# lichtla.net
KiCad netlist of a schematic drawn in EAGLE
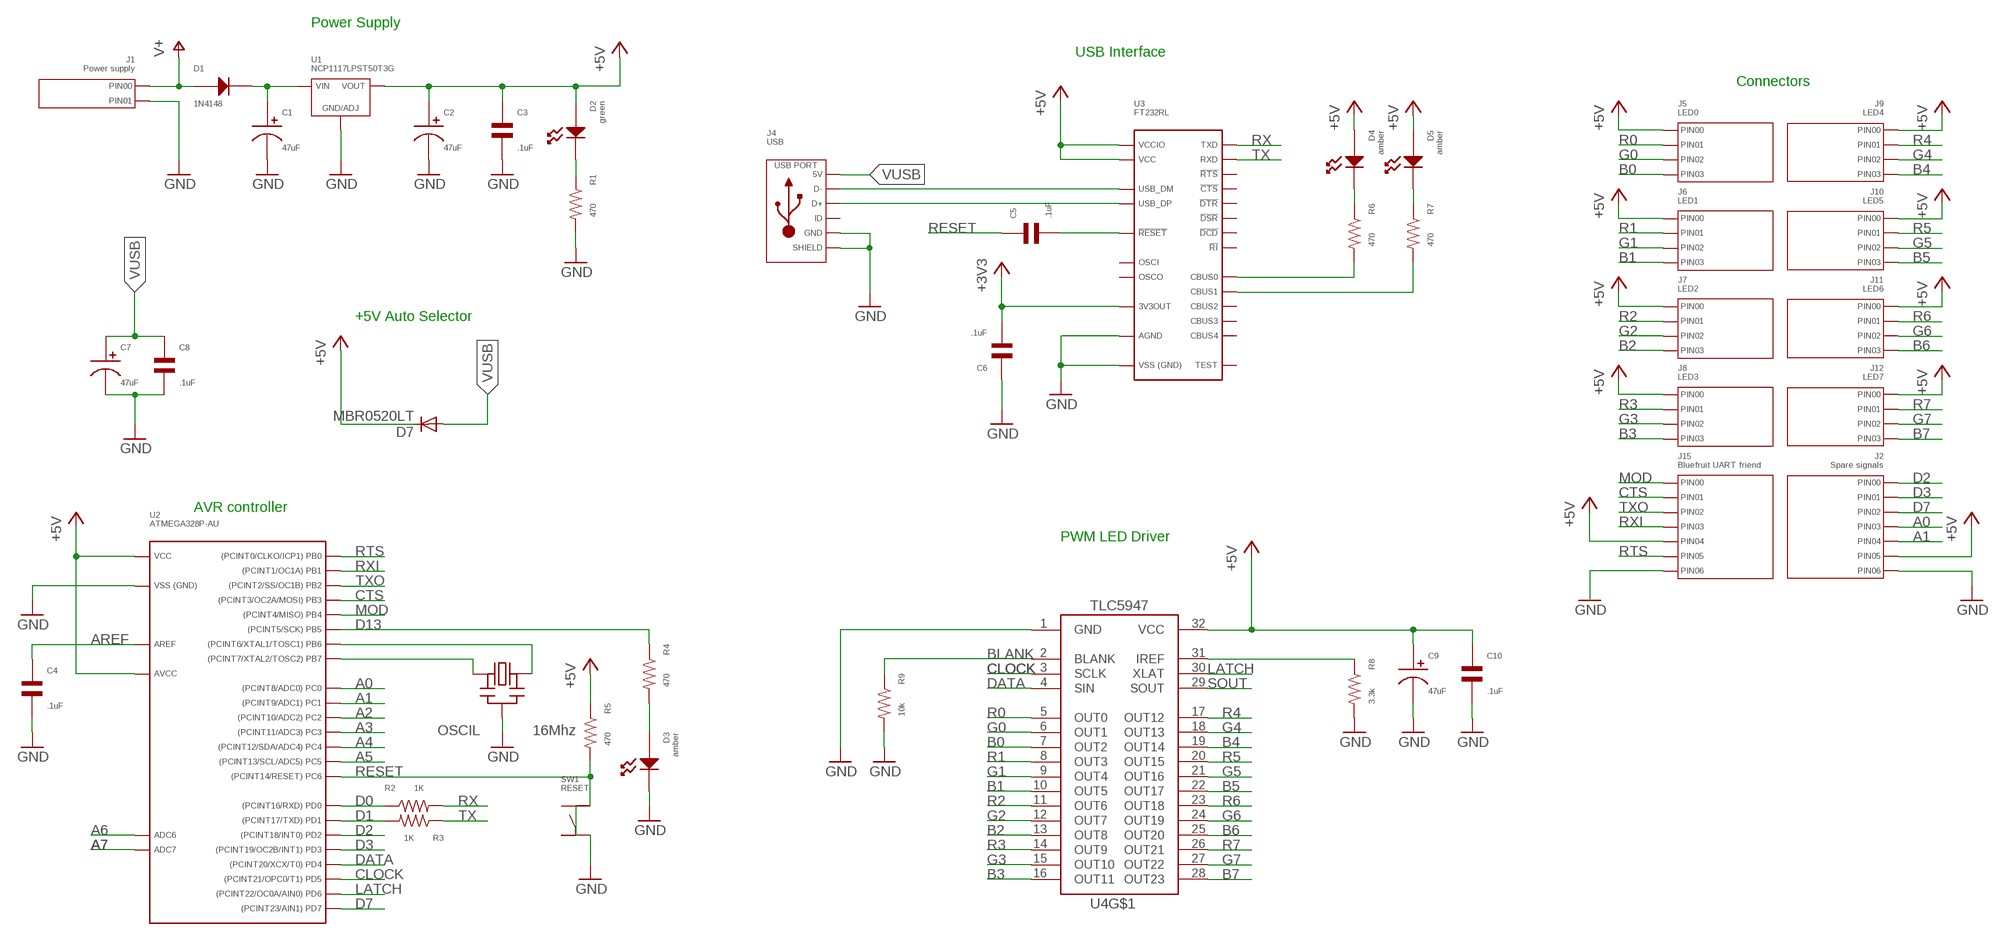
[diagram p0: schematic, sheet 1]

(export (version "E")
  (design (tool "Eeschema 10.0.6"))
  (components
    (comp (ref "C1")
      (value "47uF")
      (footprint "eagle-import:CP6.3MM")
      (libsource (lib "eagle-import") (part "CAPACITOR_P_6.3MM"))
    )
    (comp (ref "C2")
      (value "47uF")
      (footprint "eagle-import:CP6.3MM")
      (libsource (lib "eagle-import") (part "CAPACITOR_P_6.3MM"))
    )
    (comp (ref "C3")
      (value ".1uF")
      (footprint "eagle-import:C0402")
      (libsource (lib "eagle-import") (part "CAPACITOR_NP_0402"))
    )
    (comp (ref "C4")
      (value ".1uF")
      (footprint "eagle-import:C0402")
      (libsource (lib "eagle-import") (part "CAPACITOR_NP_0402"))
    )
    (comp (ref "C5")
      (value ".1uF")
      (footprint "eagle-import:C0402")
      (libsource (lib "eagle-import") (part "CAPACITOR_NP_0402"))
    )
    (comp (ref "C6")
      (value ".1uF")
      (footprint "eagle-import:C0402")
      (libsource (lib "eagle-import") (part "CAPACITOR_NP_0402"))
    )
    (comp (ref "C7")
      (value "47uF")
      (footprint "eagle-import:CP6.3MM")
      (libsource (lib "eagle-import") (part "CAPACITOR_P_6.3MM"))
    )
    (comp (ref "C8")
      (value ".1uF")
      (footprint "eagle-import:C0402")
      (libsource (lib "eagle-import") (part "CAPACITOR_NP_0402"))
    )
    (comp (ref "C9")
      (value "47uF")
      (footprint "eagle-import:CP6.3MM")
      (libsource (lib "eagle-import") (part "CAPACITOR_P_6.3MM"))
    )
    (comp (ref "C10")
      (value ".1uF")
      (footprint "eagle-import:C0402")
      (libsource (lib "eagle-import") (part "CAPACITOR_NP_0402"))
    )
    (comp (ref "D1")
      (value "1N4148")
      (footprint "eagle-import:SOD-123")
      (libsource (lib "eagle-import") (part "DIODE_SOD-123"))
    )
    (comp (ref "D2")
      (value "green")
      (footprint "eagle-import:LED0805")
      (libsource (lib "eagle-import") (part "LED_SINGLE_0805"))
    )
    (comp (ref "D3")
      (value "amber")
      (footprint "eagle-import:LED0805")
      (libsource (lib "eagle-import") (part "LED_SINGLE_0805"))
    )
    (comp (ref "D4")
      (value "amber")
      (footprint "eagle-import:LED0805")
      (libsource (lib "eagle-import") (part "LED_SINGLE_0805"))
    )
    (comp (ref "D5")
      (value "amber")
      (footprint "eagle-import:LED0805")
      (libsource (lib "eagle-import") (part "LED_SINGLE_0805"))
    )
    (comp (ref "D7")
      (value "MBR0520LT")
      (footprint "eagle-import:SOD123")
      (libsource (lib "eagle-import") (part "MBR0520LT"))
    )
    (comp (ref "J1")
      (value "Power supply")
      (footprint "eagle-import:PTH_2.54MM_01X02")
      (libsource (lib "eagle-import") (part "HEADER_01X02_PTH_2.54MM"))
    )
    (comp (ref "J2")
      (value "Spare signals")
      (footprint "eagle-import:PTH_2.54MM_01X07")
      (libsource (lib "eagle-import") (part "HEADER_01X07_PTH_2.54MM"))
    )
    (comp (ref "J4")
      (value "USB")
      (footprint "eagle-import:MICROUSB-RIGHT")
      (libsource (lib "eagle-import") (part "USB_MICRO_RIGHT"))
    )
    (comp (ref "J5")
      (value "LED0")
      (footprint "eagle-import:PTH_2.54MM_01X04")
      (libsource (lib "eagle-import") (part "HEADER_01X04_PTH_2.54MM"))
    )
    (comp (ref "J6")
      (value "LED1")
      (footprint "eagle-import:PTH_2.54MM_01X04")
      (libsource (lib "eagle-import") (part "HEADER_01X04_PTH_2.54MM"))
    )
    (comp (ref "J7")
      (value "LED2")
      (footprint "eagle-import:PTH_2.54MM_01X04")
      (libsource (lib "eagle-import") (part "HEADER_01X04_PTH_2.54MM"))
    )
    (comp (ref "J8")
      (value "LED3")
      (footprint "eagle-import:PTH_2.54MM_01X04")
      (libsource (lib "eagle-import") (part "HEADER_01X04_PTH_2.54MM"))
    )
    (comp (ref "J9")
      (value "LED4")
      (footprint "eagle-import:PTH_2.54MM_01X04")
      (libsource (lib "eagle-import") (part "HEADER_01X04_PTH_2.54MM"))
    )
    (comp (ref "J10")
      (value "LED5")
      (footprint "eagle-import:PTH_2.54MM_01X04")
      (libsource (lib "eagle-import") (part "HEADER_01X04_PTH_2.54MM"))
    )
    (comp (ref "J11")
      (value "LED6")
      (footprint "eagle-import:PTH_2.54MM_01X04")
      (libsource (lib "eagle-import") (part "HEADER_01X04_PTH_2.54MM"))
    )
    (comp (ref "J12")
      (value "LED7")
      (footprint "eagle-import:PTH_2.54MM_01X04")
      (libsource (lib "eagle-import") (part "HEADER_01X04_PTH_2.54MM"))
    )
    (comp (ref "J15")
      (value "Bluefruit UART friend")
      (footprint "eagle-import:PTH_2.54MM_01X07")
      (libsource (lib "eagle-import") (part "HEADER_01X07_PTH_2.54MM"))
    )
    (comp (ref "OSCIL")
      (value "16Mhz")
      (footprint "eagle-import:AWCSR")
      (libsource (lib "eagle-import") (part "CERMOSCILL-AWCSR"))
    )
    (comp (ref "R1")
      (value "470")
      (footprint "eagle-import:R0805")
      (libsource (lib "eagle-import") (part "RESISTOR_0805"))
    )
    (comp (ref "R2")
      (value "1K")
      (footprint "eagle-import:R0805")
      (libsource (lib "eagle-import") (part "RESISTOR_0805"))
    )
    (comp (ref "R3")
      (value "1K")
      (footprint "eagle-import:R0805")
      (libsource (lib "eagle-import") (part "RESISTOR_0805"))
    )
    (comp (ref "R4")
      (value "470")
      (footprint "eagle-import:R0805")
      (libsource (lib "eagle-import") (part "RESISTOR_0805"))
    )
    (comp (ref "R5")
      (value "470")
      (footprint "eagle-import:R0805")
      (libsource (lib "eagle-import") (part "RESISTOR_0805"))
    )
    (comp (ref "R6")
      (value "470")
      (footprint "eagle-import:R0805")
      (libsource (lib "eagle-import") (part "RESISTOR_0805"))
    )
    (comp (ref "R7")
      (value "470")
      (footprint "eagle-import:R0805")
      (libsource (lib "eagle-import") (part "RESISTOR_0805"))
    )
    (comp (ref "R8")
      (value "3.3k")
      (footprint "eagle-import:R0805")
      (libsource (lib "eagle-import") (part "RESISTOR_0805"))
    )
    (comp (ref "R9")
      (value "10k")
      (footprint "eagle-import:R0805")
      (libsource (lib "eagle-import") (part "RESISTOR_0805"))
    )
    (comp (ref "SW1")
      (value "RESET")
      (footprint "eagle-import:TACT6MM")
      (libsource (lib "eagle-import") (part "TACT_6MM"))
    )
    (comp (ref "U1")
      (value "NCP1117LPST50T3G")
      (footprint "eagle-import:SOT-223-3")
      (libsource (lib "eagle-import") (part "NCP1117LPST50T3G"))
    )
    (comp (ref "U2")
      (value "ATMEGA328P-AU")
      (footprint "eagle-import:TQFP32")
      (libsource (lib "eagle-import") (part "ATMEGA328P-AU"))
    )
    (comp (ref "U3")
      (value "FT232RL")
      (footprint "eagle-import:SSOP28")
      (libsource (lib "eagle-import") (part "FT232RL"))
    )
    (comp (ref "U4")
      (value "TLC5947-DAP")
      (footprint "eagle-import:HTSSOP32DAP")
      (libsource (lib "eagle-import") (part "TLC5947-DAP"))
    )
  )
  (nets
    (net (code "1") (name "+3V3") (class "Default")
      (node (ref "C6") (pin "P$2") (pinfunction "P$2_P$2") (pintype "passive"))
      (node (ref "U3") (pin "P$17") (pinfunction "3V3OUT_P$17") (pintype "bidirectional"))
    )
    (net (code "2") (name "+5V") (class "Default")
      (node (ref "C10") (pin "P$1") (pinfunction "P$1_P$1") (pintype "passive"))
      (node (ref "C2") (pin "P$1") (pinfunction "P$1_P$1") (pintype "passive"))
      (node (ref "C3") (pin "P$1") (pinfunction "P$1_P$1") (pintype "passive"))
      (node (ref "C9") (pin "P$1") (pinfunction "P$1_P$1") (pintype "passive"))
      (node (ref "D2") (pin "ANODE") (pinfunction "ANODE_ANODE") (pintype "power_in"))
      (node (ref "D4") (pin "ANODE") (pinfunction "ANODE_ANODE") (pintype "power_in"))
      (node (ref "D5") (pin "ANODE") (pinfunction "ANODE_ANODE") (pintype "power_in"))
      (node (ref "D7") (pin "C") (pinfunction "C_C") (pintype "passive"))
      (node (ref "J10") (pin "P$1") (pinfunction "PIN0_P$1") (pintype "bidirectional"))
      (node (ref "J11") (pin "P$1") (pinfunction "PIN0_P$1") (pintype "bidirectional"))
      (node (ref "J12") (pin "P$1") (pinfunction "PIN0_P$1") (pintype "bidirectional"))
      (node (ref "J15") (pin "P$5") (pinfunction "PIN4_P$5") (pintype "bidirectional"))
      (node (ref "J2") (pin "P$6") (pinfunction "PIN5_P$6") (pintype "bidirectional"))
      (node (ref "J5") (pin "P$1") (pinfunction "PIN0_P$1") (pintype "bidirectional"))
      (node (ref "J6") (pin "P$1") (pinfunction "PIN0_P$1") (pintype "bidirectional"))
      (node (ref "J7") (pin "P$1") (pinfunction "PIN0_P$1") (pintype "bidirectional"))
      (node (ref "J8") (pin "P$1") (pinfunction "PIN0_P$1") (pintype "bidirectional"))
      (node (ref "J9") (pin "P$1") (pinfunction "PIN0_P$1") (pintype "bidirectional"))
      (node (ref "R5") (pin "P$1") (pinfunction "P$1_P$1") (pintype "passive"))
      (node (ref "U1") (pin "P$1") (pinfunction "VOUT_P$1") (pintype "bidirectional"))
      (node (ref "U1") (pin "P$3") (pinfunction "VOUT_P$3") (pintype "bidirectional"))
      (node (ref "U2") (pin "P$18") (pinfunction "AVCC_P$18") (pintype "power_in"))
      (node (ref "U2") (pin "P$4") (pinfunction "VCC_P$4") (pintype "power_in"))
      (node (ref "U2") (pin "P$6") (pinfunction "VCC_P$6") (pintype "power_in"))
      (node (ref "U3") (pin "P$20") (pinfunction "VCC_P$20") (pintype "bidirectional"))
      (node (ref "U3") (pin "P$4") (pinfunction "VCCIO_P$4") (pintype "bidirectional"))
      (node (ref "U4") (pin "32") (pinfunction "VCC_32") (pintype "power_in"))
    )
    (net (code "3") (name "/A0") (class "Default")
      (node (ref "J2") (pin "P$4") (pinfunction "PIN3_P$4") (pintype "bidirectional"))
      (node (ref "U2") (pin "P$23") (pinfunction "PC0_P$23") (pintype "bidirectional"))
    )
    (net (code "4") (name "/A1") (class "Default")
      (node (ref "J2") (pin "P$5") (pinfunction "PIN4_P$5") (pintype "bidirectional"))
      (node (ref "U2") (pin "P$24") (pinfunction "PC1_P$24") (pintype "bidirectional"))
    )
    (net (code "5") (name "/A2") (class "Default")
      (node (ref "U2") (pin "P$25") (pinfunction "PC2_P$25") (pintype "bidirectional"))
    )
    (net (code "6") (name "/A3") (class "Default")
      (node (ref "U2") (pin "P$26") (pinfunction "PC3_P$26") (pintype "bidirectional"))
    )
    (net (code "7") (name "/A4") (class "Default")
      (node (ref "U2") (pin "P$27") (pinfunction "PC4_P$27") (pintype "bidirectional"))
    )
    (net (code "8") (name "/A5") (class "Default")
      (node (ref "U2") (pin "P$28") (pinfunction "PC5_P$28") (pintype "bidirectional"))
    )
    (net (code "9") (name "/A6") (class "Default")
      (node (ref "U2") (pin "P$19") (pinfunction "ADC6_P$19") (pintype "bidirectional"))
    )
    (net (code "10") (name "/A7") (class "Default")
      (node (ref "U2") (pin "P$22") (pinfunction "ADC7_P$22") (pintype "bidirectional"))
    )
    (net (code "11") (name "/AREF") (class "Default")
      (node (ref "C4") (pin "P$1") (pinfunction "P$1_P$1") (pintype "passive"))
      (node (ref "U2") (pin "P$20") (pinfunction "AREF_P$20") (pintype "power_in"))
    )
    (net (code "12") (name "/B0") (class "Default")
      (node (ref "J5") (pin "P$4") (pinfunction "PIN3_P$4") (pintype "bidirectional"))
      (node (ref "U4") (pin "7") (pinfunction "OUT2_7") (pintype "open_collector"))
    )
    (net (code "13") (name "/B1") (class "Default")
      (node (ref "J6") (pin "P$4") (pinfunction "PIN3_P$4") (pintype "bidirectional"))
      (node (ref "U4") (pin "10") (pinfunction "OUT5_10") (pintype "open_collector"))
    )
    (net (code "14") (name "/B2") (class "Default")
      (node (ref "J7") (pin "P$4") (pinfunction "PIN3_P$4") (pintype "bidirectional"))
      (node (ref "U4") (pin "13") (pinfunction "OUT8_13") (pintype "open_collector"))
    )
    (net (code "15") (name "/B3") (class "Default")
      (node (ref "J8") (pin "P$4") (pinfunction "PIN3_P$4") (pintype "bidirectional"))
      (node (ref "U4") (pin "16") (pinfunction "OUT11_16") (pintype "open_collector"))
    )
    (net (code "16") (name "/B4") (class "Default")
      (node (ref "J9") (pin "P$4") (pinfunction "PIN3_P$4") (pintype "bidirectional"))
      (node (ref "U4") (pin "19") (pinfunction "OUT14_19") (pintype "open_collector"))
    )
    (net (code "17") (name "/B5") (class "Default")
      (node (ref "J10") (pin "P$4") (pinfunction "PIN3_P$4") (pintype "bidirectional"))
      (node (ref "U4") (pin "22") (pinfunction "OUT17_22") (pintype "open_collector"))
    )
    (net (code "18") (name "/B6") (class "Default")
      (node (ref "J11") (pin "P$4") (pinfunction "PIN3_P$4") (pintype "bidirectional"))
      (node (ref "U4") (pin "25") (pinfunction "OUT20_25") (pintype "open_collector"))
    )
    (net (code "19") (name "/B7") (class "Default")
      (node (ref "J12") (pin "P$4") (pinfunction "PIN3_P$4") (pintype "bidirectional"))
      (node (ref "U4") (pin "28") (pinfunction "OUT23_28") (pintype "open_collector"))
    )
    (net (code "20") (name "/BLANK") (class "Default")
      (node (ref "R9") (pin "P$1") (pinfunction "P$1_P$1") (pintype "passive"))
      (node (ref "U4") (pin "2") (pinfunction "BLANK_2") (pintype "input"))
    )
    (net (code "21") (name "/CLOCK") (class "Default")
      (node (ref "U2") (pin "P$9") (pinfunction "PD5_P$9") (pintype "bidirectional"))
      (node (ref "U4") (pin "3") (pinfunction "SCLK_3") (pintype "input"))
    )
    (net (code "22") (name "/CTS") (class "Default")
      (node (ref "J15") (pin "P$2") (pinfunction "PIN1_P$2") (pintype "bidirectional"))
      (node (ref "U2") (pin "P$15") (pinfunction "PB3_P$15") (pintype "bidirectional"))
    )
    (net (code "23") (name "/D0") (class "Default")
      (node (ref "R2") (pin "P$1") (pinfunction "P$1_P$1") (pintype "passive"))
      (node (ref "U2") (pin "P$30") (pinfunction "PD0_P$30") (pintype "bidirectional"))
    )
    (net (code "24") (name "/D1") (class "Default")
      (node (ref "R3") (pin "P$2") (pinfunction "P$2_P$2") (pintype "passive"))
      (node (ref "U2") (pin "P$31") (pinfunction "PD1_P$31") (pintype "bidirectional"))
    )
    (net (code "25") (name "/D2") (class "Default")
      (node (ref "J2") (pin "P$1") (pinfunction "PIN0_P$1") (pintype "bidirectional"))
      (node (ref "U2") (pin "P$32") (pinfunction "PD2_P$32") (pintype "bidirectional"))
    )
    (net (code "26") (name "/D3") (class "Default")
      (node (ref "J2") (pin "P$2") (pinfunction "PIN1_P$2") (pintype "bidirectional"))
      (node (ref "U2") (pin "P$1") (pinfunction "PD3_P$1") (pintype "bidirectional"))
    )
    (net (code "27") (name "/D7") (class "Default")
      (node (ref "J2") (pin "P$3") (pinfunction "PIN2_P$3") (pintype "bidirectional"))
      (node (ref "U2") (pin "P$11") (pinfunction "PD7_P$11") (pintype "bidirectional"))
    )
    (net (code "28") (name "/D13") (class "Default")
      (node (ref "R4") (pin "P$1") (pinfunction "P$1_P$1") (pintype "passive"))
      (node (ref "U2") (pin "P$17") (pinfunction "PB5_P$17") (pintype "bidirectional"))
    )
    (net (code "29") (name "/DATA") (class "Default")
      (node (ref "U2") (pin "P$2") (pinfunction "PD4_P$2") (pintype "bidirectional"))
      (node (ref "U4") (pin "4") (pinfunction "SIN_4") (pintype "input"))
    )
    (net (code "30") (name "/G0") (class "Default")
      (node (ref "J5") (pin "P$3") (pinfunction "PIN2_P$3") (pintype "bidirectional"))
      (node (ref "U4") (pin "6") (pinfunction "OUT1_6") (pintype "open_collector"))
    )
    (net (code "31") (name "/G1") (class "Default")
      (node (ref "J6") (pin "P$3") (pinfunction "PIN2_P$3") (pintype "bidirectional"))
      (node (ref "U4") (pin "9") (pinfunction "OUT4_9") (pintype "open_collector"))
    )
    (net (code "32") (name "/G2") (class "Default")
      (node (ref "J7") (pin "P$3") (pinfunction "PIN2_P$3") (pintype "bidirectional"))
      (node (ref "U4") (pin "12") (pinfunction "OUT7_12") (pintype "open_collector"))
    )
    (net (code "33") (name "/G3") (class "Default")
      (node (ref "J8") (pin "P$3") (pinfunction "PIN2_P$3") (pintype "bidirectional"))
      (node (ref "U4") (pin "15") (pinfunction "OUT10_15") (pintype "open_collector"))
    )
    (net (code "34") (name "/G4") (class "Default")
      (node (ref "J9") (pin "P$3") (pinfunction "PIN2_P$3") (pintype "bidirectional"))
      (node (ref "U4") (pin "18") (pinfunction "OUT13_18") (pintype "open_collector"))
    )
    (net (code "35") (name "/G5") (class "Default")
      (node (ref "J10") (pin "P$3") (pinfunction "PIN2_P$3") (pintype "bidirectional"))
      (node (ref "U4") (pin "21") (pinfunction "OUT16_21") (pintype "open_collector"))
    )
    (net (code "36") (name "/G6") (class "Default")
      (node (ref "J11") (pin "P$3") (pinfunction "PIN2_P$3") (pintype "bidirectional"))
      (node (ref "U4") (pin "24") (pinfunction "OUT19_24") (pintype "open_collector"))
    )
    (net (code "37") (name "/G7") (class "Default")
      (node (ref "J12") (pin "P$3") (pinfunction "PIN2_P$3") (pintype "bidirectional"))
      (node (ref "U4") (pin "27") (pinfunction "OUT22_27") (pintype "open_collector"))
    )
    (net (code "38") (name "/LATCH") (class "Default")
      (node (ref "U2") (pin "P$10") (pinfunction "PD6_P$10") (pintype "bidirectional"))
      (node (ref "U4") (pin "30") (pinfunction "XLAT_30") (pintype "input"))
    )
    (net (code "39") (name "/MOD") (class "Default")
      (node (ref "J15") (pin "P$1") (pinfunction "PIN0_P$1") (pintype "bidirectional"))
      (node (ref "U2") (pin "P$16") (pinfunction "PB4_P$16") (pintype "bidirectional"))
    )
    (net (code "40") (name "/R0") (class "Default")
      (node (ref "J5") (pin "P$2") (pinfunction "PIN1_P$2") (pintype "bidirectional"))
      (node (ref "U4") (pin "5") (pinfunction "OUT0_5") (pintype "open_collector"))
    )
    (net (code "41") (name "/R1") (class "Default")
      (node (ref "J6") (pin "P$2") (pinfunction "PIN1_P$2") (pintype "bidirectional"))
      (node (ref "U4") (pin "8") (pinfunction "OUT3_8") (pintype "open_collector"))
    )
    (net (code "42") (name "/R2") (class "Default")
      (node (ref "J7") (pin "P$2") (pinfunction "PIN1_P$2") (pintype "bidirectional"))
      (node (ref "U4") (pin "11") (pinfunction "OUT6_11") (pintype "open_collector"))
    )
    (net (code "43") (name "/R3") (class "Default")
      (node (ref "J8") (pin "P$2") (pinfunction "PIN1_P$2") (pintype "bidirectional"))
      (node (ref "U4") (pin "14") (pinfunction "OUT9_14") (pintype "open_collector"))
    )
    (net (code "44") (name "/R4") (class "Default")
      (node (ref "J9") (pin "P$2") (pinfunction "PIN1_P$2") (pintype "bidirectional"))
      (node (ref "U4") (pin "17") (pinfunction "OUT12_17") (pintype "open_collector"))
    )
    (net (code "45") (name "/R5") (class "Default")
      (node (ref "J10") (pin "P$2") (pinfunction "PIN1_P$2") (pintype "bidirectional"))
      (node (ref "U4") (pin "20") (pinfunction "OUT15_20") (pintype "open_collector"))
    )
    (net (code "46") (name "/R6") (class "Default")
      (node (ref "J11") (pin "P$2") (pinfunction "PIN1_P$2") (pintype "bidirectional"))
      (node (ref "U4") (pin "23") (pinfunction "OUT18_23") (pintype "open_collector"))
    )
    (net (code "47") (name "/R7") (class "Default")
      (node (ref "J12") (pin "P$2") (pinfunction "PIN1_P$2") (pintype "bidirectional"))
      (node (ref "U4") (pin "26") (pinfunction "OUT21_26") (pintype "open_collector"))
    )
    (net (code "48") (name "/RESET") (class "Default")
      (node (ref "C5") (pin "P$1") (pinfunction "P$1_P$1") (pintype "passive"))
      (node (ref "R5") (pin "P$2") (pinfunction "P$2_P$2") (pintype "passive"))
      (node (ref "SW1") (pin "P$2") (pinfunction "P$2_P$2") (pintype "bidirectional"))
      (node (ref "U2") (pin "P$29") (pinfunction "PC6_P$29") (pintype "bidirectional"))
    )
    (net (code "49") (name "/RTS") (class "Default")
      (node (ref "J15") (pin "P$6") (pinfunction "PIN5_P$6") (pintype "bidirectional"))
      (node (ref "U2") (pin "P$12") (pinfunction "PB0_P$12") (pintype "bidirectional"))
    )
    (net (code "50") (name "/RX") (class "Default")
      (node (ref "R2") (pin "P$2") (pinfunction "P$2_P$2") (pintype "passive"))
      (node (ref "U3") (pin "P$1") (pinfunction "TXD_P$1") (pintype "bidirectional"))
    )
    (net (code "51") (name "/RXI") (class "Default")
      (node (ref "J15") (pin "P$4") (pinfunction "PIN3_P$4") (pintype "bidirectional"))
      (node (ref "U2") (pin "P$13") (pinfunction "PB1_P$13") (pintype "bidirectional"))
    )
    (net (code "52") (name "/SOUT") (class "Default")
      (node (ref "U4") (pin "29") (pinfunction "SOUT_29") (pintype "output"))
    )
    (net (code "53") (name "/TX") (class "Default")
      (node (ref "R3") (pin "P$1") (pinfunction "P$1_P$1") (pintype "passive"))
      (node (ref "U3") (pin "P$5") (pinfunction "RXD_P$5") (pintype "bidirectional"))
    )
    (net (code "54") (name "/TXO") (class "Default")
      (node (ref "J15") (pin "P$3") (pinfunction "PIN2_P$3") (pintype "bidirectional"))
      (node (ref "U2") (pin "P$14") (pinfunction "PB2_P$14") (pintype "bidirectional"))
    )
    (net (code "55") (name "GND") (class "Default")
      (node (ref "C1") (pin "P$2") (pinfunction "P$2_P$2") (pintype "passive"))
      (node (ref "C10") (pin "P$2") (pinfunction "P$2_P$2") (pintype "passive"))
      (node (ref "C2") (pin "P$2") (pinfunction "P$2_P$2") (pintype "passive"))
      (node (ref "C3") (pin "P$2") (pinfunction "P$2_P$2") (pintype "passive"))
      (node (ref "C4") (pin "P$2") (pinfunction "P$2_P$2") (pintype "passive"))
      (node (ref "C6") (pin "P$1") (pinfunction "P$1_P$1") (pintype "passive"))
      (node (ref "C7") (pin "P$2") (pinfunction "P$2_P$2") (pintype "passive"))
      (node (ref "C8") (pin "P$2") (pinfunction "P$2_P$2") (pintype "passive"))
      (node (ref "C9") (pin "P$2") (pinfunction "P$2_P$2") (pintype "passive"))
      (node (ref "D3") (pin "CATHODE") (pinfunction "CATHODE_CATHODE") (pintype "power_in"))
      (node (ref "J1") (pin "P$1") (pinfunction "PIN1_P$1") (pintype "bidirectional"))
      (node (ref "J15") (pin "P$7") (pinfunction "PIN6_P$7") (pintype "bidirectional"))
      (node (ref "J2") (pin "P$7") (pinfunction "PIN6_P$7") (pintype "bidirectional"))
      (node (ref "J4") (pin "5") (pinfunction "GND_5") (pintype "power_in"))
      (node (ref "J4") (pin "S1") (pinfunction "SLD_S1") (pintype "power_in"))
      (node (ref "J4") (pin "S2") (pinfunction "SLD_S2") (pintype "power_in"))
      (node (ref "J4") (pin "S3") (pinfunction "SLD_S3") (pintype "power_in"))
      (node (ref "J4") (pin "S4") (pinfunction "SLD_S4") (pintype "power_in"))
      (node (ref "J4") (pin "S5") (pinfunction "SLD_S5") (pintype "power_in"))
      (node (ref "J4") (pin "S6") (pinfunction "SLD_S6") (pintype "power_in"))
      (node (ref "J4") (pin "S7") (pinfunction "SLD_S7") (pintype "power_in"))
      (node (ref "J4") (pin "S8") (pinfunction "SLD_S8") (pintype "power_in"))
      (node (ref "OSCIL") (pin "2") (pinfunction "GND_2") (pintype "bidirectional"))
      (node (ref "R1") (pin "P$2") (pinfunction "P$2_P$2") (pintype "passive"))
      (node (ref "R8") (pin "P$2") (pinfunction "P$2_P$2") (pintype "passive"))
      (node (ref "R9") (pin "P$2") (pinfunction "P$2_P$2") (pintype "passive"))
      (node (ref "SW1") (pin "P$4") (pinfunction "P$4_P$4") (pintype "bidirectional"))
      (node (ref "U1") (pin "P$2") (pinfunction "GND/ADJ_P$2") (pintype "bidirectional"))
      (node (ref "U2") (pin "P$21") (pinfunction "GND_P$21") (pintype "power_in"))
      (node (ref "U2") (pin "P$3") (pinfunction "GND_P$3") (pintype "power_in"))
      (node (ref "U2") (pin "P$5") (pinfunction "GND_P$5") (pintype "power_in"))
      (node (ref "U3") (pin "P$18") (pinfunction "GND_P$18") (pintype "bidirectional"))
      (node (ref "U3") (pin "P$21") (pinfunction "GND_P$21") (pintype "bidirectional"))
      (node (ref "U3") (pin "P$25") (pinfunction "AGND_P$25") (pintype "bidirectional"))
      (node (ref "U3") (pin "P$7") (pinfunction "GND_P$7") (pintype "bidirectional"))
      (node (ref "U4") (pin "1") (pinfunction "GND_1") (pintype "power_in"))
    )
    (net (code "56") (name "Net-(D2-PadCATHODE)") (class "Default")
      (node (ref "D2") (pin "CATHODE") (pinfunction "CATHODE_CATHODE") (pintype "power_in"))
      (node (ref "R1") (pin "P$1") (pinfunction "P$1_P$1") (pintype "passive"))
    )
    (net (code "57") (name "Net-(D3-PadANODE)") (class "Default")
      (node (ref "D3") (pin "ANODE") (pinfunction "ANODE_ANODE") (pintype "power_in"))
      (node (ref "R4") (pin "P$2") (pinfunction "P$2_P$2") (pintype "passive"))
    )
    (net (code "58") (name "Net-(D4-PadCATHODE)") (class "Default")
      (node (ref "D4") (pin "CATHODE") (pinfunction "CATHODE_CATHODE") (pintype "power_in"))
      (node (ref "R6") (pin "P$1") (pinfunction "P$1_P$1") (pintype "passive"))
    )
    (net (code "59") (name "Net-(D5-PadCATHODE)") (class "Default")
      (node (ref "D5") (pin "CATHODE") (pinfunction "CATHODE_CATHODE") (pintype "power_in"))
      (node (ref "R7") (pin "P$1") (pinfunction "P$1_P$1") (pintype "passive"))
    )
    (net (code "60") (name "Net-(J4-D+)") (class "Default")
      (node (ref "J4") (pin "3") (pinfunction "D+_3") (pintype "bidirectional"))
      (node (ref "U3") (pin "P$15") (pinfunction "USBDP_P$15") (pintype "bidirectional"))
    )
    (net (code "61") (name "Net-(J4-D-)") (class "Default")
      (node (ref "J4") (pin "2") (pinfunction "D-_2") (pintype "bidirectional"))
      (node (ref "U3") (pin "P$16") (pinfunction "USBDM_P$16") (pintype "bidirectional"))
    )
    (net (code "62") (name "Net-(OSCIL-IN)") (class "Default")
      (node (ref "OSCIL") (pin "1") (pinfunction "IN_1") (pintype "bidirectional"))
      (node (ref "U2") (pin "P$8") (pinfunction "PB7_P$8") (pintype "bidirectional"))
    )
    (net (code "63") (name "Net-(OSCIL-OUT)") (class "Default")
      (node (ref "OSCIL") (pin "3") (pinfunction "OUT_3") (pintype "bidirectional"))
      (node (ref "U2") (pin "P$7") (pinfunction "PB6_P$7") (pintype "bidirectional"))
    )
    (net (code "64") (name "Net-(U1-VIN)") (class "Default")
      (node (ref "C1") (pin "P$1") (pinfunction "P$1_P$1") (pintype "passive"))
      (node (ref "D1") (pin "CATHODE") (pinfunction "CATHODE_CATHODE") (pintype "bidirectional"))
      (node (ref "U1") (pin "P$4") (pinfunction "VIN_P$4") (pintype "bidirectional"))
    )
    (net (code "65") (name "Net-(U3-CBUS0)") (class "Default")
      (node (ref "R6") (pin "P$2") (pinfunction "P$2_P$2") (pintype "passive"))
      (node (ref "U3") (pin "P$23") (pinfunction "CBUS0_P$23") (pintype "bidirectional"))
    )
    (net (code "66") (name "Net-(U3-CBUS1)") (class "Default")
      (node (ref "R7") (pin "P$2") (pinfunction "P$2_P$2") (pintype "passive"))
      (node (ref "U3") (pin "P$22") (pinfunction "CBUS1_P$22") (pintype "bidirectional"))
    )
    (net (code "67") (name "Net-(U3-~{RESET})") (class "Default")
      (node (ref "C5") (pin "P$2") (pinfunction "P$2_P$2") (pintype "passive"))
      (node (ref "U3") (pin "P$19") (pinfunction "~{RESET}_P$19") (pintype "bidirectional"))
    )
    (net (code "68") (name "Net-(U4A-IREF)") (class "Default")
      (node (ref "R8") (pin "P$1") (pinfunction "P$1_P$1") (pintype "passive"))
      (node (ref "U4") (pin "31") (pinfunction "IREF_31") (pintype "bidirectional"))
    )
    (net (code "69") (name "V+") (class "Default")
      (node (ref "D1") (pin "ANODE") (pinfunction "ANODE_ANODE") (pintype "bidirectional"))
      (node (ref "J1") (pin "P$2") (pinfunction "PIN0_P$2") (pintype "bidirectional"))
    )
    (net (code "70") (name "VUSB") (class "Default")
      (node (ref "C7") (pin "P$1") (pinfunction "P$1_P$1") (pintype "passive"))
      (node (ref "C8") (pin "P$1") (pinfunction "P$1_P$1") (pintype "passive"))
      (node (ref "D7") (pin "A") (pinfunction "A_A") (pintype "passive"))
      (node (ref "J4") (pin "1") (pinfunction "5V_1") (pintype "power_in"))
    )
    (net (code "71") (name "unconnected-(J4-ID-Pad4)") (class "Default")
      (node (ref "J4") (pin "4") (pinfunction "ID_4") (pintype "bidirectional"))
    )
    (net (code "72") (name "unconnected-(SW1-PadP$1)") (class "Default")
      (node (ref "SW1") (pin "P$1") (pinfunction "P$1_P$1") (pintype "bidirectional"))
    )
    (net (code "73") (name "unconnected-(SW1-PadP$3)") (class "Default")
      (node (ref "SW1") (pin "P$3") (pinfunction "P$3_P$3") (pintype "bidirectional"))
    )
    (net (code "74") (name "unconnected-(U3-CBUS2-PadP$13)") (class "Default")
      (node (ref "U3") (pin "P$13") (pinfunction "CBUS2_P$13") (pintype "bidirectional"))
    )
    (net (code "75") (name "unconnected-(U3-CBUS3-PadP$14)") (class "Default")
      (node (ref "U3") (pin "P$14") (pinfunction "CBUS3_P$14") (pintype "bidirectional"))
    )
    (net (code "76") (name "unconnected-(U3-CBUS4-PadP$12)") (class "Default")
      (node (ref "U3") (pin "P$12") (pinfunction "CBUS4_P$12") (pintype "bidirectional"))
    )
    (net (code "77") (name "unconnected-(U3-OSCI-PadP$27)") (class "Default")
      (node (ref "U3") (pin "P$27") (pinfunction "OSCI_P$27") (pintype "bidirectional"))
    )
    (net (code "78") (name "unconnected-(U3-OSCO-PadP$28)") (class "Default")
      (node (ref "U3") (pin "P$28") (pinfunction "OSCO_P$28") (pintype "bidirectional"))
    )
    (net (code "79") (name "unconnected-(U3-TEST-PadP$26)") (class "Default")
      (node (ref "U3") (pin "P$26") (pinfunction "TEST_P$26") (pintype "bidirectional"))
    )
    (net (code "80") (name "unconnected-(U3-~{CTS}-PadP$11)") (class "Default")
      (node (ref "U3") (pin "P$11") (pinfunction "~{CTS}_P$11") (pintype "bidirectional"))
    )
    (net (code "81") (name "unconnected-(U3-~{DCD}-PadP$10)") (class "Default")
      (node (ref "U3") (pin "P$10") (pinfunction "~{DCD}_P$10") (pintype "bidirectional"))
    )
    (net (code "82") (name "unconnected-(U3-~{DSR}-PadP$9)") (class "Default")
      (node (ref "U3") (pin "P$9") (pinfunction "~{DSR}_P$9") (pintype "bidirectional"))
    )
    (net (code "83") (name "unconnected-(U3-~{DTR}-PadP$2)") (class "Default")
      (node (ref "U3") (pin "P$2") (pinfunction "~{DTR}_P$2") (pintype "bidirectional"))
    )
    (net (code "84") (name "unconnected-(U3-~{RI}-PadP$6)") (class "Default")
      (node (ref "U3") (pin "P$6") (pinfunction "~{RI}_P$6") (pintype "bidirectional"))
    )
    (net (code "85") (name "unconnected-(U3-~{RTS}-PadP$3)") (class "Default")
      (node (ref "U3") (pin "P$3") (pinfunction "~{RTS}_P$3") (pintype "bidirectional"))
    )
  )
)
